# MCP3423.net
KiCad netlist of a schematic drawn in Altium Designer
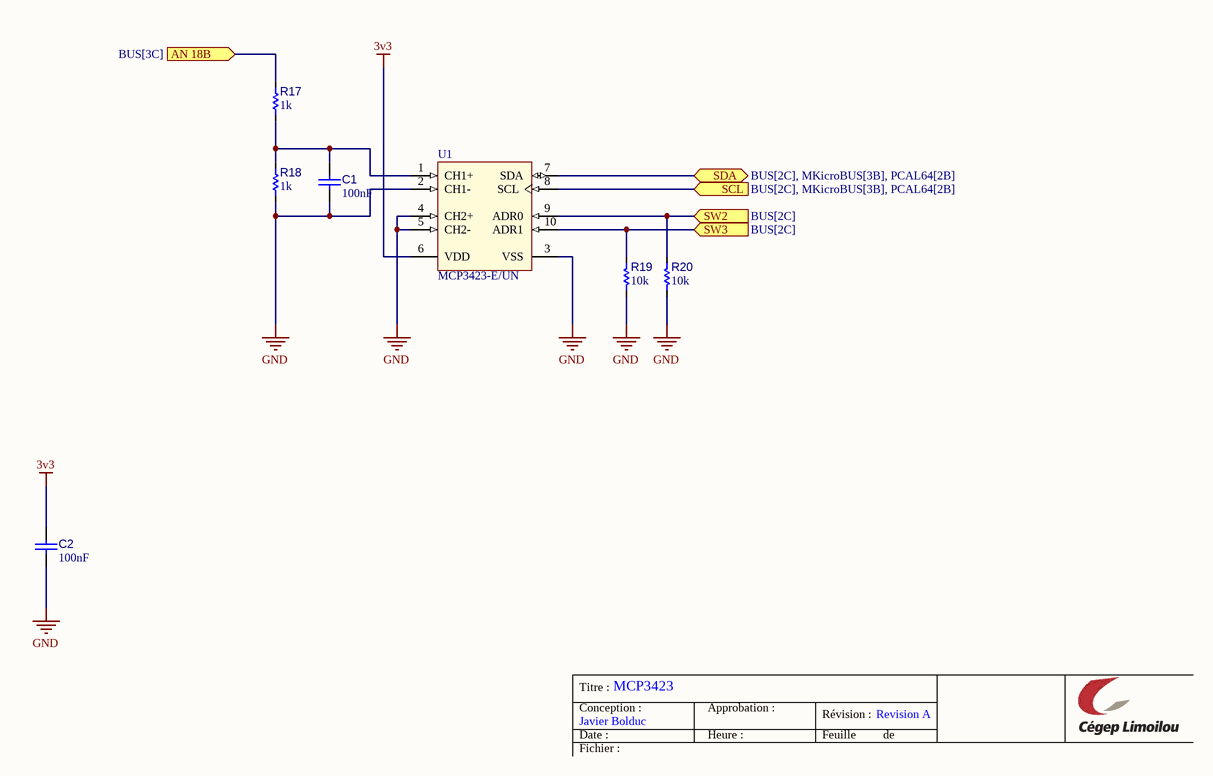
[diagram p0: MCP3423.schdoc]

(export (version "E")
  (design (tool "Eeschema 10.0.6"))
  (components
    (comp (ref "C1")
      (value "100nF")
      (footprint "C_1608[0603]")
      (description "Capacitor type 1")
      (fields (field (name "TOLERANCE") "10%") (field (name "Comment") "CAP CER 100nF 50V 0603"))
      (libsource (lib "TEP-AltiumLib-Passives-RLC") (part "capacitor"))
    )
    (comp (ref "C2")
      (value "100nF")
      (footprint "C_1608[0603]")
      (description "Capacitor type 1")
      (fields (field (name "TOLERANCE") "10%") (field (name "Comment") "CAP CER 100nF 50V 0603"))
      (libsource (lib "TEP-AltiumLib-Passives-RLC") (part "capacitor"))
    )
    (comp (ref "R17")
      (value "1k")
      (footprint "R_1608[0603]")
      (description "Resistor type 1")
      (fields (field (name "TOLERANCE") "1%") (field (name "Comment") "Res 1k 1% 0603"))
      (libsource (lib "TEP-AltiumLib-Passives-RLC") (part "resistor"))
    )
    (comp (ref "R18")
      (value "1k")
      (footprint "R_1608[0603]")
      (description "Resistor type 1")
      (fields (field (name "TOLERANCE") "1%") (field (name "Comment") "Res 1k 1% 0603"))
      (libsource (lib "TEP-AltiumLib-Passives-RLC") (part "resistor"))
    )
    (comp (ref "R19")
      (value "10k")
      (footprint "R_1608[0603]")
      (description "Resistor type 1")
      (fields (field (name "TOLERANCE") "1%") (field (name "Comment") "Res 10k 1% 0603"))
      (libsource (lib "TEP-AltiumLib-Passives-RLC") (part "resistor"))
    )
    (comp (ref "R20")
      (value "10k")
      (footprint "R_1608[0603]")
      (description "Resistor type 1")
      (fields (field (name "TOLERANCE") "1%") (field (name "Comment") "Res 10k 1% 0603"))
      (libsource (lib "TEP-AltiumLib-Passives-RLC") (part "resistor"))
    )
    (comp (ref "U1")
      (value "MCP3423-E/UN")
      (footprint "U_MSOP50P300X500-10(RM-10)_WO-TP")
      (description "CAN Controller Stand-Alone With SPI, 18-Pin PDIP")
      (libsource (lib "TEP-AltiumLib-ICs") (part "U_MCP3423-E/UN"))
    )
  )
  (nets
    (net (code "1") (name "/AN 18B") (class "Default")
      (node (ref "R17") (pin "1") (pinfunction "1_1") (pintype "passive"))
    )
    (net (code "2") (name "/SCL") (class "Default")
      (node (ref "U1") (pin "8") (pinfunction "SCL_8") (pintype "input"))
    )
    (net (code "3") (name "/SDA") (class "Default")
      (node (ref "U1") (pin "7") (pinfunction "SDA_7") (pintype "bidirectional"))
    )
    (net (code "4") (name "/SW2") (class "Default")
      (node (ref "R20") (pin "1") (pinfunction "1_1") (pintype "passive"))
      (node (ref "U1") (pin "9") (pinfunction "ADR0_9") (pintype "input"))
    )
    (net (code "5") (name "/SW3") (class "Default")
      (node (ref "R19") (pin "1") (pinfunction "1_1") (pintype "passive"))
      (node (ref "U1") (pin "10") (pinfunction "ADR1_10") (pintype "input"))
    )
    (net (code "6") (name "3v3") (class "Default")
      (node (ref "C2") (pin "2") (pinfunction "2_2") (pintype "passive"))
      (node (ref "U1") (pin "6") (pinfunction "VDD_6") (pintype "power_in"))
    )
    (net (code "7") (name "GND") (class "Default")
      (node (ref "C1") (pin "2") (pinfunction "2_2") (pintype "passive"))
      (node (ref "C2") (pin "1") (pinfunction "1_1") (pintype "passive"))
      (node (ref "R18") (pin "2") (pinfunction "2_2") (pintype "passive"))
      (node (ref "R19") (pin "2") (pinfunction "2_2") (pintype "passive"))
      (node (ref "R20") (pin "2") (pinfunction "2_2") (pintype "passive"))
      (node (ref "U1") (pin "2") (pinfunction "CH1-_2") (pintype "input"))
      (node (ref "U1") (pin "3") (pinfunction "VSS_3") (pintype "power_in"))
      (node (ref "U1") (pin "4") (pinfunction "CH2+_4") (pintype "input"))
      (node (ref "U1") (pin "5") (pinfunction "CH2-_5") (pintype "input"))
    )
    (net (code "8") (name "Net-(U1-CH1+)") (class "Default")
      (node (ref "C1") (pin "1") (pinfunction "1_1") (pintype "passive"))
      (node (ref "R17") (pin "2") (pinfunction "2_2") (pintype "passive"))
      (node (ref "R18") (pin "1") (pinfunction "1_1") (pintype "passive"))
      (node (ref "U1") (pin "1") (pinfunction "CH1+_1") (pintype "input"))
    )
  )
)
